# FC-Shield.net
KiCad netlist of a schematic drawn in Altium Designer
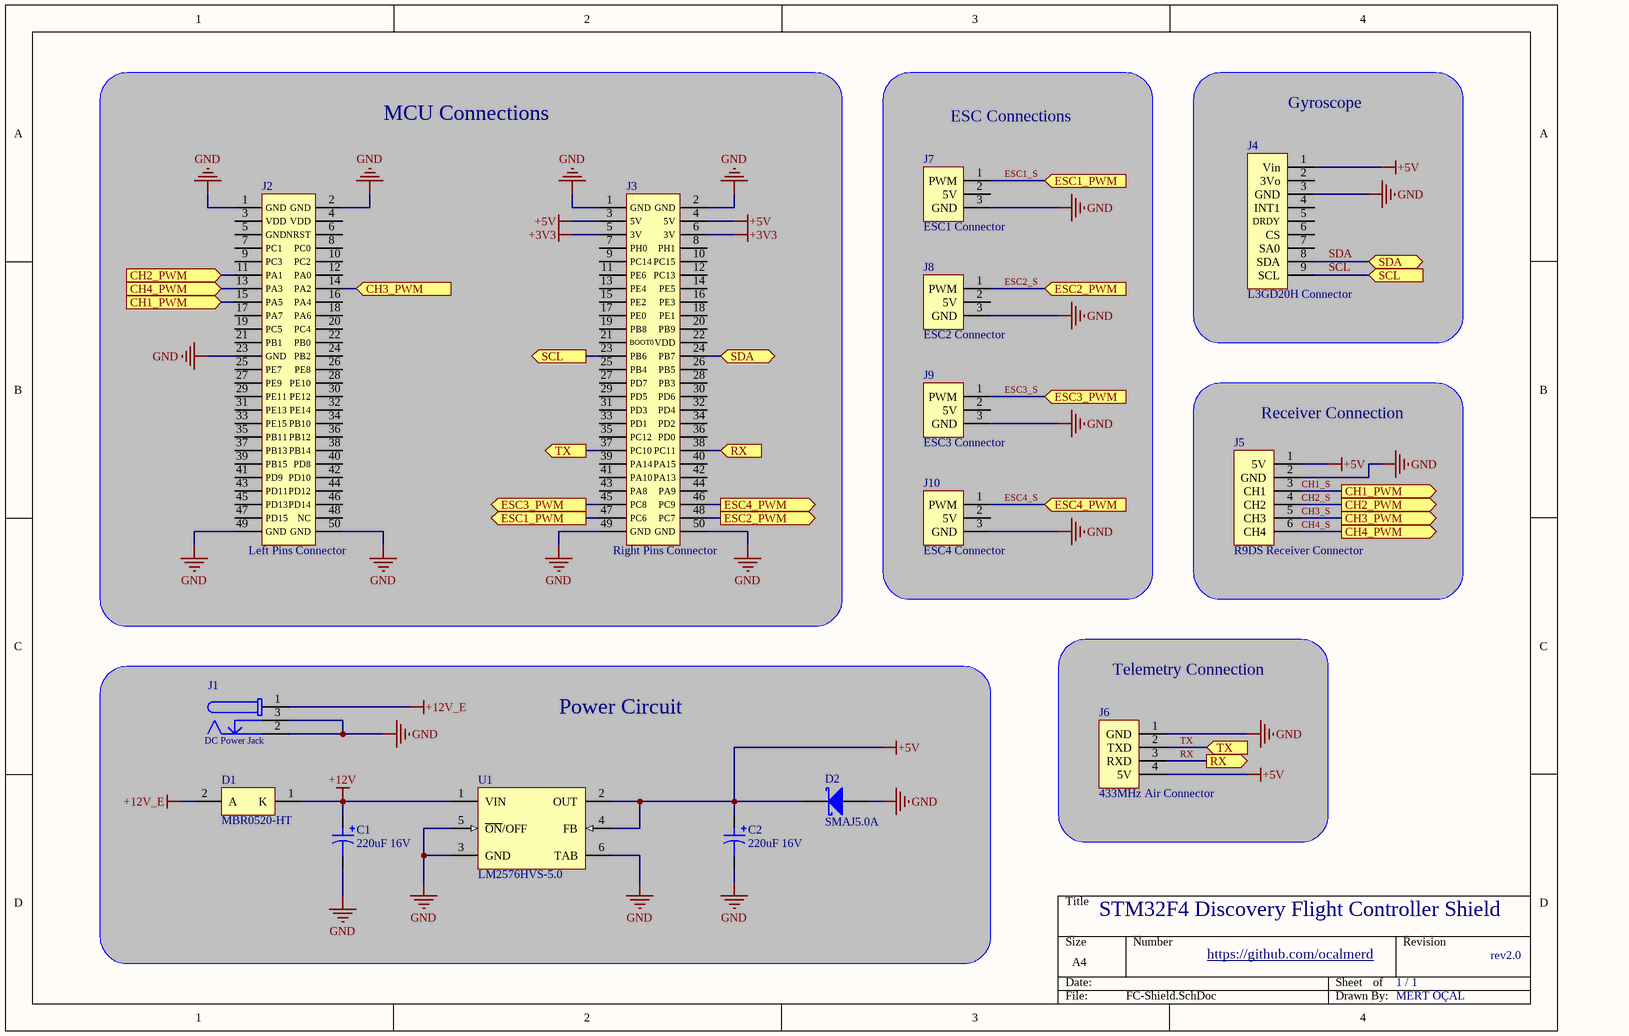
[diagram p0: FC-Shield.SchDoc]

(export (version "E")
  (design (tool "Eeschema 10.0.6"))
  (components
    (comp (ref "C1")
      (value "CAP ALUM 220UF 20% 16V SMD")
      (footprint "CAP ALUM 6.6MM")
      (description "220µF 16V Aluminum Electrolytic Capacitors Radial, Can - SMD  1000 Hrs @ 105°C")
      (fields (field (name "DEGER") "220uF 16V"))
      (libsource (lib "Kondansatör") (part "100uF 16V Aluminum(POL)"))
    )
    (comp (ref "C2")
      (value "CAP ALUM 220UF 20% 16V SMD")
      (footprint "CAP ALUM 6.6MM")
      (description "220µF 16V Aluminum Electrolytic Capacitors Radial, Can - SMD  1000 Hrs @ 105°C")
      (fields (field (name "DEGER") "220uF 16V"))
      (libsource (lib "Kondansatör") (part "100uF 16V Aluminum(POL)"))
    )
    (comp (ref "D1")
      (value "MBR0520-HT")
      (footprint "ONSC-SOD-123-2-425-04_V")
      (description "20V 0.5A Schottky Power Rectifier, 2-Pin SOD-123, Tape and Reel")
      (fields (field (name "MANUFACTURER") "On Semiconductor") (field (name "PARTNUMBER") "MBR0520LT1"))
      (libsource (lib "ON Semi Schottky Diodes & Schottky Rectifiers") (part "MBR0520LT1"))
    )
    (comp (ref "D2")
      (value "SMAJ5.0A TVS Diyot")
      (footprint "DO214AC SMA")
      (description "Schottky Rectifier")
      (fields (field (name "DEGER") "SMAJ5.0A"))
      (libsource (lib "Diyot") (part "SMAJ5.0A"))
    )
    (comp (ref "J1")
      (value "DC Power Jack")
      (footprint "694106301002")
      (description "DC Power Jack Connector WR-DC, Male, Right Angled, THT, 5 A, 24 V")
      (fields (field (name "PART NUMBER") "694106301002") (field (name "PUBLISHER") "Wurth Elektronik"))
      (libsource (lib "WR-DC_Power_Jack_Connectors") (part "694106301002"))
    )
    (comp (ref "J2")
      (value "Left Pins Connector")
      (footprint "HDR2X25")
      (description "Header, 25-Pin, Dual row")
      (fields (field (name "PUBLISHER") "Altium Limited"))
      (libsource (lib "Miscellaneous Connectors") (part "Header 25X2"))
    )
    (comp (ref "J3")
      (value "Right Pins Connector")
      (footprint "HDR2X25")
      (description "Header, 25-Pin, Dual row")
      (fields (field (name "PUBLISHER") "Altium Limited"))
      (libsource (lib "Miscellaneous Connectors") (part "Header 25X2"))
    )
    (comp (ref "J4")
      (value "L3GD20H Connector")
      (footprint "HDR1X9")
      (description "Header, 9-Pin")
      (fields (field (name "PUBLISHER") "Altium Limited"))
      (libsource (lib "Miscellaneous Connectors") (part "Header 9"))
    )
    (comp (ref "J5")
      (value "R9DS Receiver Connector")
      (footprint "HDR1X6H")
      (description "Header, 6-Pin, Right Angle")
      (fields (field (name "PUBLISHER") "Altium Limited"))
      (libsource (lib "Miscellaneous Connectors") (part "Header 6H"))
    )
    (comp (ref "J6")
      (value "433MHz Air Connector")
      (footprint "HDR1X4H")
      (description "Header, 4-Pin, Right Angle")
      (fields (field (name "PUBLISHER") "Altium Limited"))
      (libsource (lib "Miscellaneous Connectors") (part "Header 4H"))
    )
    (comp (ref "J7")
      (value "ESC1 Connector")
      (footprint "HDR1X3H")
      (description "Header, 3-Pin, Right Angle")
      (fields (field (name "PUBLISHER") "Altium Limited"))
      (libsource (lib "Miscellaneous Connectors") (part "Header 3H"))
    )
    (comp (ref "J8")
      (value "ESC2 Connector")
      (footprint "HDR1X3H")
      (description "Header, 3-Pin, Right Angle")
      (fields (field (name "PUBLISHER") "Altium Limited"))
      (libsource (lib "Miscellaneous Connectors") (part "Header 3H"))
    )
    (comp (ref "J9")
      (value "ESC3 Connector")
      (footprint "HDR1X3H")
      (description "Header, 3-Pin, Right Angle")
      (fields (field (name "PUBLISHER") "Altium Limited"))
      (libsource (lib "Miscellaneous Connectors") (part "Header 3H"))
    )
    (comp (ref "J10")
      (value "ESC4 Connector")
      (footprint "HDR1X3H")
      (description "Header, 3-Pin, Right Angle")
      (fields (field (name "PUBLISHER") "Altium Limited"))
      (libsource (lib "Miscellaneous Connectors") (part "Header 3H"))
    )
    (comp (ref "U1")
      (value "LM2576HVS-5.0 REG BUCK 5V 3A TO263-5")
      (footprint "TO-263-6")
      (fields (field (name "DEGER") "LM2576HVS-5.0"))
      (libsource (lib "IC") (part "LM2576HVS-5.0--"))
    )
  )
  (nets
    (net (code "1") (name "+3V3") (class "Default")
      (node (ref "J3") (pin "5") (pinfunction "GND_5") (pintype "passive"))
      (node (ref "J3") (pin "6") (pinfunction "NRST_6") (pintype "passive"))
    )
    (net (code "2") (name "+5V") (class "Default")
      (node (ref "C2") (pin "1") (pinfunction "1_1") (pintype "passive"))
      (node (ref "D2") (pin "2") (pinfunction "K_2") (pintype "passive"))
      (node (ref "J3") (pin "3") (pinfunction "VDD_3") (pintype "passive"))
      (node (ref "J3") (pin "4") (pinfunction "VDD_4") (pintype "passive"))
      (node (ref "J4") (pin "1") (pinfunction "Vin_1") (pintype "passive"))
      (node (ref "J5") (pin "1") (pinfunction "5V_1") (pintype "passive"))
      (node (ref "J6") (pin "4") (pinfunction "5V_4") (pintype "passive"))
      (node (ref "U1") (pin "2") (pinfunction "OUT_2") (pintype "power_in"))
      (node (ref "U1") (pin "4") (pinfunction "FB_4") (pintype "input"))
    )
    (net (code "3") (name "+12V") (class "Default")
      (node (ref "C1") (pin "1") (pinfunction "1_1") (pintype "passive"))
      (node (ref "D1") (pin "1") (pinfunction "K_1") (pintype "passive"))
      (node (ref "U1") (pin "1") (pinfunction "VIN_1") (pintype "power_in"))
    )
    (net (code "4") (name "+12V_E") (class "Default")
      (node (ref "D1") (pin "2") (pinfunction "A_2") (pintype "passive"))
      (node (ref "J1") (pin "1") (pinfunction "1_1") (pintype "passive"))
    )
    (net (code "5") (name "/CH1_S") (class "Default")
      (node (ref "J2") (pin "15") (pinfunction "PA5_15") (pintype "passive"))
      (node (ref "J5") (pin "3") (pinfunction "CH1_3") (pintype "passive"))
    )
    (net (code "6") (name "/CH2_S") (class "Default")
      (node (ref "J2") (pin "11") (pinfunction "PA1_11") (pintype "passive"))
      (node (ref "J5") (pin "4") (pinfunction "CH2_4") (pintype "passive"))
    )
    (net (code "7") (name "/CH3_S") (class "Default")
      (node (ref "J2") (pin "14") (pinfunction "PA2_14") (pintype "passive"))
      (node (ref "J5") (pin "5") (pinfunction "CH3_5") (pintype "passive"))
    )
    (net (code "8") (name "/CH4_S") (class "Default")
      (node (ref "J2") (pin "13") (pinfunction "PA3_13") (pintype "passive"))
      (node (ref "J5") (pin "6") (pinfunction "CH4_6") (pintype "passive"))
    )
    (net (code "9") (name "/ESC1_S") (class "Default")
      (node (ref "J3") (pin "47") (pinfunction "PD15_47") (pintype "passive"))
      (node (ref "J7") (pin "1") (pinfunction "PWM_1") (pintype "passive"))
    )
    (net (code "10") (name "/ESC2_S") (class "Default")
      (node (ref "J3") (pin "48") (pinfunction "NC_48") (pintype "passive"))
      (node (ref "J8") (pin "1") (pinfunction "PWM_1") (pintype "passive"))
    )
    (net (code "11") (name "/ESC3_S") (class "Default")
      (node (ref "J3") (pin "45") (pinfunction "PD13_45") (pintype "passive"))
      (node (ref "J9") (pin "1") (pinfunction "PWM_1") (pintype "passive"))
    )
    (net (code "12") (name "/ESC4_S") (class "Default")
      (node (ref "J10") (pin "1") (pinfunction "PWM_1") (pintype "passive"))
      (node (ref "J3") (pin "46") (pinfunction "PD14_46") (pintype "passive"))
    )
    (net (code "13") (name "/RX") (class "Default")
      (node (ref "J3") (pin "38") (pinfunction "PB14_38") (pintype "passive"))
      (node (ref "J6") (pin "3") (pinfunction "RXD_3") (pintype "passive"))
    )
    (net (code "14") (name "/SCL") (class "Default")
      (node (ref "J3") (pin "23") (pinfunction "GND_23") (pintype "passive"))
      (node (ref "J4") (pin "9") (pinfunction "SCL_9") (pintype "passive"))
    )
    (net (code "15") (name "/SDA") (class "Default")
      (node (ref "J3") (pin "24") (pinfunction "PB2_24") (pintype "passive"))
      (node (ref "J4") (pin "8") (pinfunction "SDA_8") (pintype "passive"))
    )
    (net (code "16") (name "/TX") (class "Default")
      (node (ref "J3") (pin "37") (pinfunction "PB13_37") (pintype "passive"))
      (node (ref "J6") (pin "2") (pinfunction "TXD_2") (pintype "passive"))
    )
    (net (code "17") (name "GND") (class "Default")
      (node (ref "C1") (pin "2") (pinfunction "2_2") (pintype "passive"))
      (node (ref "C2") (pin "2") (pinfunction "2_2") (pintype "passive"))
      (node (ref "D2") (pin "1") (pinfunction "A_1") (pintype "passive"))
      (node (ref "J1") (pin "2") (pinfunction "2_2") (pintype "passive"))
      (node (ref "J1") (pin "3") (pinfunction "3_3") (pintype "passive"))
      (node (ref "J10") (pin "3") (pinfunction "GND_3") (pintype "passive"))
      (node (ref "J2") (pin "1") (pinfunction "GND_1") (pintype "passive"))
      (node (ref "J2") (pin "2") (pinfunction "GND_2") (pintype "passive"))
      (node (ref "J2") (pin "23") (pinfunction "GND_23") (pintype "passive"))
      (node (ref "J2") (pin "49") (pinfunction "GND_49") (pintype "passive"))
      (node (ref "J2") (pin "50") (pinfunction "GND_50") (pintype "passive"))
      (node (ref "J3") (pin "1") (pinfunction "GND_1") (pintype "passive"))
      (node (ref "J3") (pin "2") (pinfunction "GND_2") (pintype "passive"))
      (node (ref "J3") (pin "49") (pinfunction "GND_49") (pintype "passive"))
      (node (ref "J3") (pin "50") (pinfunction "GND_50") (pintype "passive"))
      (node (ref "J4") (pin "3") (pinfunction "GND_3") (pintype "passive"))
      (node (ref "J5") (pin "2") (pinfunction "GND_2") (pintype "passive"))
      (node (ref "J6") (pin "1") (pinfunction "GND_1") (pintype "passive"))
      (node (ref "J7") (pin "3") (pinfunction "GND_3") (pintype "passive"))
      (node (ref "J8") (pin "3") (pinfunction "GND_3") (pintype "passive"))
      (node (ref "J9") (pin "3") (pinfunction "GND_3") (pintype "passive"))
      (node (ref "U1") (pin "3") (pinfunction "GND_3") (pintype "power_in"))
      (node (ref "U1") (pin "5") (pinfunction "~{ON}/OFF_5") (pintype "input"))
      (node (ref "U1") (pin "6") (pinfunction "TAB_6") (pintype "power_in"))
    )
    (net (code "18") (name "unconnected-(J2-GND-Pad5)") (class "Default")
      (node (ref "J2") (pin "5") (pinfunction "GND_5") (pintype "passive"))
    )
    (net (code "19") (name "unconnected-(J2-NC-Pad48)") (class "Default")
      (node (ref "J2") (pin "48") (pinfunction "NC_48") (pintype "passive"))
    )
    (net (code "20") (name "unconnected-(J2-NRST-Pad6)") (class "Default")
      (node (ref "J2") (pin "6") (pinfunction "NRST_6") (pintype "passive"))
    )
    (net (code "21") (name "unconnected-(J2-PA0-Pad12)") (class "Default")
      (node (ref "J2") (pin "12") (pinfunction "PA0_12") (pintype "passive"))
    )
    (net (code "22") (name "unconnected-(J2-PA4-Pad16)") (class "Default")
      (node (ref "J2") (pin "16") (pinfunction "PA4_16") (pintype "passive"))
    )
    (net (code "23") (name "unconnected-(J2-PA6-Pad18)") (class "Default")
      (node (ref "J2") (pin "18") (pinfunction "PA6_18") (pintype "passive"))
    )
    (net (code "24") (name "unconnected-(J2-PA7-Pad17)") (class "Default")
      (node (ref "J2") (pin "17") (pinfunction "PA7_17") (pintype "passive"))
    )
    (net (code "25") (name "unconnected-(J2-PB0-Pad22)") (class "Default")
      (node (ref "J2") (pin "22") (pinfunction "PB0_22") (pintype "passive"))
    )
    (net (code "26") (name "unconnected-(J2-PB1-Pad21)") (class "Default")
      (node (ref "J2") (pin "21") (pinfunction "PB1_21") (pintype "passive"))
    )
    (net (code "27") (name "unconnected-(J2-PB2-Pad24)") (class "Default")
      (node (ref "J2") (pin "24") (pinfunction "PB2_24") (pintype "passive"))
    )
    (net (code "28") (name "unconnected-(J2-PB10-Pad34)") (class "Default")
      (node (ref "J2") (pin "34") (pinfunction "PB10_34") (pintype "passive"))
    )
    (net (code "29") (name "unconnected-(J2-PB11-Pad35)") (class "Default")
      (node (ref "J2") (pin "35") (pinfunction "PB11_35") (pintype "passive"))
    )
    (net (code "30") (name "unconnected-(J2-PB12-Pad36)") (class "Default")
      (node (ref "J2") (pin "36") (pinfunction "PB12_36") (pintype "passive"))
    )
    (net (code "31") (name "unconnected-(J2-PB13-Pad37)") (class "Default")
      (node (ref "J2") (pin "37") (pinfunction "PB13_37") (pintype "passive"))
    )
    (net (code "32") (name "unconnected-(J2-PB14-Pad38)") (class "Default")
      (node (ref "J2") (pin "38") (pinfunction "PB14_38") (pintype "passive"))
    )
    (net (code "33") (name "unconnected-(J2-PB15-Pad39)") (class "Default")
      (node (ref "J2") (pin "39") (pinfunction "PB15_39") (pintype "passive"))
    )
    (net (code "34") (name "unconnected-(J2-PC0-Pad8)") (class "Default")
      (node (ref "J2") (pin "8") (pinfunction "PC0_8") (pintype "passive"))
    )
    (net (code "35") (name "unconnected-(J2-PC1-Pad7)") (class "Default")
      (node (ref "J2") (pin "7") (pinfunction "PC1_7") (pintype "passive"))
    )
    (net (code "36") (name "unconnected-(J2-PC2-Pad10)") (class "Default")
      (node (ref "J2") (pin "10") (pinfunction "PC2_10") (pintype "passive"))
    )
    (net (code "37") (name "unconnected-(J2-PC3-Pad9)") (class "Default")
      (node (ref "J2") (pin "9") (pinfunction "PC3_9") (pintype "passive"))
    )
    (net (code "38") (name "unconnected-(J2-PC4-Pad20)") (class "Default")
      (node (ref "J2") (pin "20") (pinfunction "PC4_20") (pintype "passive"))
    )
    (net (code "39") (name "unconnected-(J2-PC5-Pad19)") (class "Default")
      (node (ref "J2") (pin "19") (pinfunction "PC5_19") (pintype "passive"))
    )
    (net (code "40") (name "unconnected-(J2-PD8-Pad40)") (class "Default")
      (node (ref "J2") (pin "40") (pinfunction "PD8_40") (pintype "passive"))
    )
    (net (code "41") (name "unconnected-(J2-PD9-Pad41)") (class "Default")
      (node (ref "J2") (pin "41") (pinfunction "PD9_41") (pintype "passive"))
    )
    (net (code "42") (name "unconnected-(J2-PD10-Pad42)") (class "Default")
      (node (ref "J2") (pin "42") (pinfunction "PD10_42") (pintype "passive"))
    )
    (net (code "43") (name "unconnected-(J2-PD11-Pad43)") (class "Default")
      (node (ref "J2") (pin "43") (pinfunction "PD11_43") (pintype "passive"))
    )
    (net (code "44") (name "unconnected-(J2-PD12-Pad44)") (class "Default")
      (node (ref "J2") (pin "44") (pinfunction "PD12_44") (pintype "passive"))
    )
    (net (code "45") (name "unconnected-(J2-PD13-Pad45)") (class "Default")
      (node (ref "J2") (pin "45") (pinfunction "PD13_45") (pintype "passive"))
    )
    (net (code "46") (name "unconnected-(J2-PD14-Pad46)") (class "Default")
      (node (ref "J2") (pin "46") (pinfunction "PD14_46") (pintype "passive"))
    )
    (net (code "47") (name "unconnected-(J2-PD15-Pad47)") (class "Default")
      (node (ref "J2") (pin "47") (pinfunction "PD15_47") (pintype "passive"))
    )
    (net (code "48") (name "unconnected-(J2-PE7-Pad25)") (class "Default")
      (node (ref "J2") (pin "25") (pinfunction "PE7_25") (pintype "passive"))
    )
    (net (code "49") (name "unconnected-(J2-PE8-Pad26)") (class "Default")
      (node (ref "J2") (pin "26") (pinfunction "PE8_26") (pintype "passive"))
    )
    (net (code "50") (name "unconnected-(J2-PE9-Pad27)") (class "Default")
      (node (ref "J2") (pin "27") (pinfunction "PE9_27") (pintype "passive"))
    )
    (net (code "51") (name "unconnected-(J2-PE10-Pad28)") (class "Default")
      (node (ref "J2") (pin "28") (pinfunction "PE10_28") (pintype "passive"))
    )
    (net (code "52") (name "unconnected-(J2-PE11-Pad29)") (class "Default")
      (node (ref "J2") (pin "29") (pinfunction "PE11_29") (pintype "passive"))
    )
    (net (code "53") (name "unconnected-(J2-PE12-Pad30)") (class "Default")
      (node (ref "J2") (pin "30") (pinfunction "PE12_30") (pintype "passive"))
    )
    (net (code "54") (name "unconnected-(J2-PE13-Pad31)") (class "Default")
      (node (ref "J2") (pin "31") (pinfunction "PE13_31") (pintype "passive"))
    )
    (net (code "55") (name "unconnected-(J2-PE14-Pad32)") (class "Default")
      (node (ref "J2") (pin "32") (pinfunction "PE14_32") (pintype "passive"))
    )
    (net (code "56") (name "unconnected-(J2-PE15-Pad33)") (class "Default")
      (node (ref "J2") (pin "33") (pinfunction "PE15_33") (pintype "passive"))
    )
    (net (code "57") (name "unconnected-(J2-VDD-Pad3)") (class "Default")
      (node (ref "J2") (pin "3") (pinfunction "VDD_3") (pintype "passive"))
    )
    (net (code "58") (name "unconnected-(J2-VDD-Pad4)") (class "Default")
      (node (ref "J2") (pin "4") (pinfunction "VDD_4") (pintype "passive"))
    )
    (net (code "59") (name "unconnected-(J3-PA0-Pad12)") (class "Default")
      (node (ref "J3") (pin "12") (pinfunction "PA0_12") (pintype "passive"))
    )
    (net (code "60") (name "unconnected-(J3-PA1-Pad11)") (class "Default")
      (node (ref "J3") (pin "11") (pinfunction "PA1_11") (pintype "passive"))
    )
    (net (code "61") (name "unconnected-(J3-PA2-Pad14)") (class "Default")
      (node (ref "J3") (pin "14") (pinfunction "PA2_14") (pintype "passive"))
    )
    (net (code "62") (name "unconnected-(J3-PA3-Pad13)") (class "Default")
      (node (ref "J3") (pin "13") (pinfunction "PA3_13") (pintype "passive"))
    )
    (net (code "63") (name "unconnected-(J3-PA4-Pad16)") (class "Default")
      (node (ref "J3") (pin "16") (pinfunction "PA4_16") (pintype "passive"))
    )
    (net (code "64") (name "unconnected-(J3-PA5-Pad15)") (class "Default")
      (node (ref "J3") (pin "15") (pinfunction "PA5_15") (pintype "passive"))
    )
    (net (code "65") (name "unconnected-(J3-PA6-Pad18)") (class "Default")
      (node (ref "J3") (pin "18") (pinfunction "PA6_18") (pintype "passive"))
    )
    (net (code "66") (name "unconnected-(J3-PA7-Pad17)") (class "Default")
      (node (ref "J3") (pin "17") (pinfunction "PA7_17") (pintype "passive"))
    )
    (net (code "67") (name "unconnected-(J3-PB0-Pad22)") (class "Default")
      (node (ref "J3") (pin "22") (pinfunction "PB0_22") (pintype "passive"))
    )
    (net (code "68") (name "unconnected-(J3-PB1-Pad21)") (class "Default")
      (node (ref "J3") (pin "21") (pinfunction "PB1_21") (pintype "passive"))
    )
    (net (code "69") (name "unconnected-(J3-PB10-Pad34)") (class "Default")
      (node (ref "J3") (pin "34") (pinfunction "PB10_34") (pintype "passive"))
    )
    (net (code "70") (name "unconnected-(J3-PB11-Pad35)") (class "Default")
      (node (ref "J3") (pin "35") (pinfunction "PB11_35") (pintype "passive"))
    )
    (net (code "71") (name "unconnected-(J3-PB12-Pad36)") (class "Default")
      (node (ref "J3") (pin "36") (pinfunction "PB12_36") (pintype "passive"))
    )
    (net (code "72") (name "unconnected-(J3-PB15-Pad39)") (class "Default")
      (node (ref "J3") (pin "39") (pinfunction "PB15_39") (pintype "passive"))
    )
    (net (code "73") (name "unconnected-(J3-PC0-Pad8)") (class "Default")
      (node (ref "J3") (pin "8") (pinfunction "PC0_8") (pintype "passive"))
    )
    (net (code "74") (name "unconnected-(J3-PC1-Pad7)") (class "Default")
      (node (ref "J3") (pin "7") (pinfunction "PC1_7") (pintype "passive"))
    )
    (net (code "75") (name "unconnected-(J3-PC2-Pad10)") (class "Default")
      (node (ref "J3") (pin "10") (pinfunction "PC2_10") (pintype "passive"))
    )
    (net (code "76") (name "unconnected-(J3-PC3-Pad9)") (class "Default")
      (node (ref "J3") (pin "9") (pinfunction "PC3_9") (pintype "passive"))
    )
    (net (code "77") (name "unconnected-(J3-PC4-Pad20)") (class "Default")
      (node (ref "J3") (pin "20") (pinfunction "PC4_20") (pintype "passive"))
    )
    (net (code "78") (name "unconnected-(J3-PC5-Pad19)") (class "Default")
      (node (ref "J3") (pin "19") (pinfunction "PC5_19") (pintype "passive"))
    )
    (net (code "79") (name "unconnected-(J3-PD8-Pad40)") (class "Default")
      (node (ref "J3") (pin "40") (pinfunction "PD8_40") (pintype "passive"))
    )
    (net (code "80") (name "unconnected-(J3-PD9-Pad41)") (class "Default")
      (node (ref "J3") (pin "41") (pinfunction "PD9_41") (pintype "passive"))
    )
    (net (code "81") (name "unconnected-(J3-PD10-Pad42)") (class "Default")
      (node (ref "J3") (pin "42") (pinfunction "PD10_42") (pintype "passive"))
    )
    (net (code "82") (name "unconnected-(J3-PD11-Pad43)") (class "Default")
      (node (ref "J3") (pin "43") (pinfunction "PD11_43") (pintype "passive"))
    )
    (net (code "83") (name "unconnected-(J3-PD12-Pad44)") (class "Default")
      (node (ref "J3") (pin "44") (pinfunction "PD12_44") (pintype "passive"))
    )
    (net (code "84") (name "unconnected-(J3-PE7-Pad25)") (class "Default")
      (node (ref "J3") (pin "25") (pinfunction "PE7_25") (pintype "passive"))
    )
    (net (code "85") (name "unconnected-(J3-PE8-Pad26)") (class "Default")
      (node (ref "J3") (pin "26") (pinfunction "PE8_26") (pintype "passive"))
    )
    (net (code "86") (name "unconnected-(J3-PE9-Pad27)") (class "Default")
      (node (ref "J3") (pin "27") (pinfunction "PE9_27") (pintype "passive"))
    )
    (net (code "87") (name "unconnected-(J3-PE10-Pad28)") (class "Default")
      (node (ref "J3") (pin "28") (pinfunction "PE10_28") (pintype "passive"))
    )
    (net (code "88") (name "unconnected-(J3-PE11-Pad29)") (class "Default")
      (node (ref "J3") (pin "29") (pinfunction "PE11_29") (pintype "passive"))
    )
    (net (code "89") (name "unconnected-(J3-PE12-Pad30)") (class "Default")
      (node (ref "J3") (pin "30") (pinfunction "PE12_30") (pintype "passive"))
    )
    (net (code "90") (name "unconnected-(J3-PE13-Pad31)") (class "Default")
      (node (ref "J3") (pin "31") (pinfunction "PE13_31") (pintype "passive"))
    )
    (net (code "91") (name "unconnected-(J3-PE14-Pad32)") (class "Default")
      (node (ref "J3") (pin "32") (pinfunction "PE14_32") (pintype "passive"))
    )
    (net (code "92") (name "unconnected-(J3-PE15-Pad33)") (class "Default")
      (node (ref "J3") (pin "33") (pinfunction "PE15_33") (pintype "passive"))
    )
    (net (code "93") (name "unconnected-(J4-3Vo-Pad2)") (class "Default")
      (node (ref "J4") (pin "2") (pinfunction "3Vo_2") (pintype "passive"))
    )
    (net (code "94") (name "unconnected-(J4-CS-Pad6)") (class "Default")
      (node (ref "J4") (pin "6") (pinfunction "CS_6") (pintype "passive"))
    )
    (net (code "95") (name "unconnected-(J4-DRDY-Pad5)") (class "Default")
      (node (ref "J4") (pin "5") (pinfunction "DRDY_5") (pintype "passive"))
    )
    (net (code "96") (name "unconnected-(J4-INT1-Pad4)") (class "Default")
      (node (ref "J4") (pin "4") (pinfunction "INT1_4") (pintype "passive"))
    )
    (net (code "97") (name "unconnected-(J4-SA0-Pad7)") (class "Default")
      (node (ref "J4") (pin "7") (pinfunction "SA0_7") (pintype "passive"))
    )
    (net (code "98") (name "unconnected-(J7-5V-Pad2)") (class "Default")
      (node (ref "J7") (pin "2") (pinfunction "5V_2") (pintype "passive"))
    )
    (net (code "99") (name "unconnected-(J8-5V-Pad2)") (class "Default")
      (node (ref "J8") (pin "2") (pinfunction "5V_2") (pintype "passive"))
    )
    (net (code "100") (name "unconnected-(J9-5V-Pad2)") (class "Default")
      (node (ref "J9") (pin "2") (pinfunction "5V_2") (pintype "passive"))
    )
    (net (code "101") (name "unconnected-(J10-5V-Pad2)") (class "Default")
      (node (ref "J10") (pin "2") (pinfunction "5V_2") (pintype "passive"))
    )
  )
)
